# Review_PCD_1_2.net
KiCad netlist of a schematic drawn in EAGLE
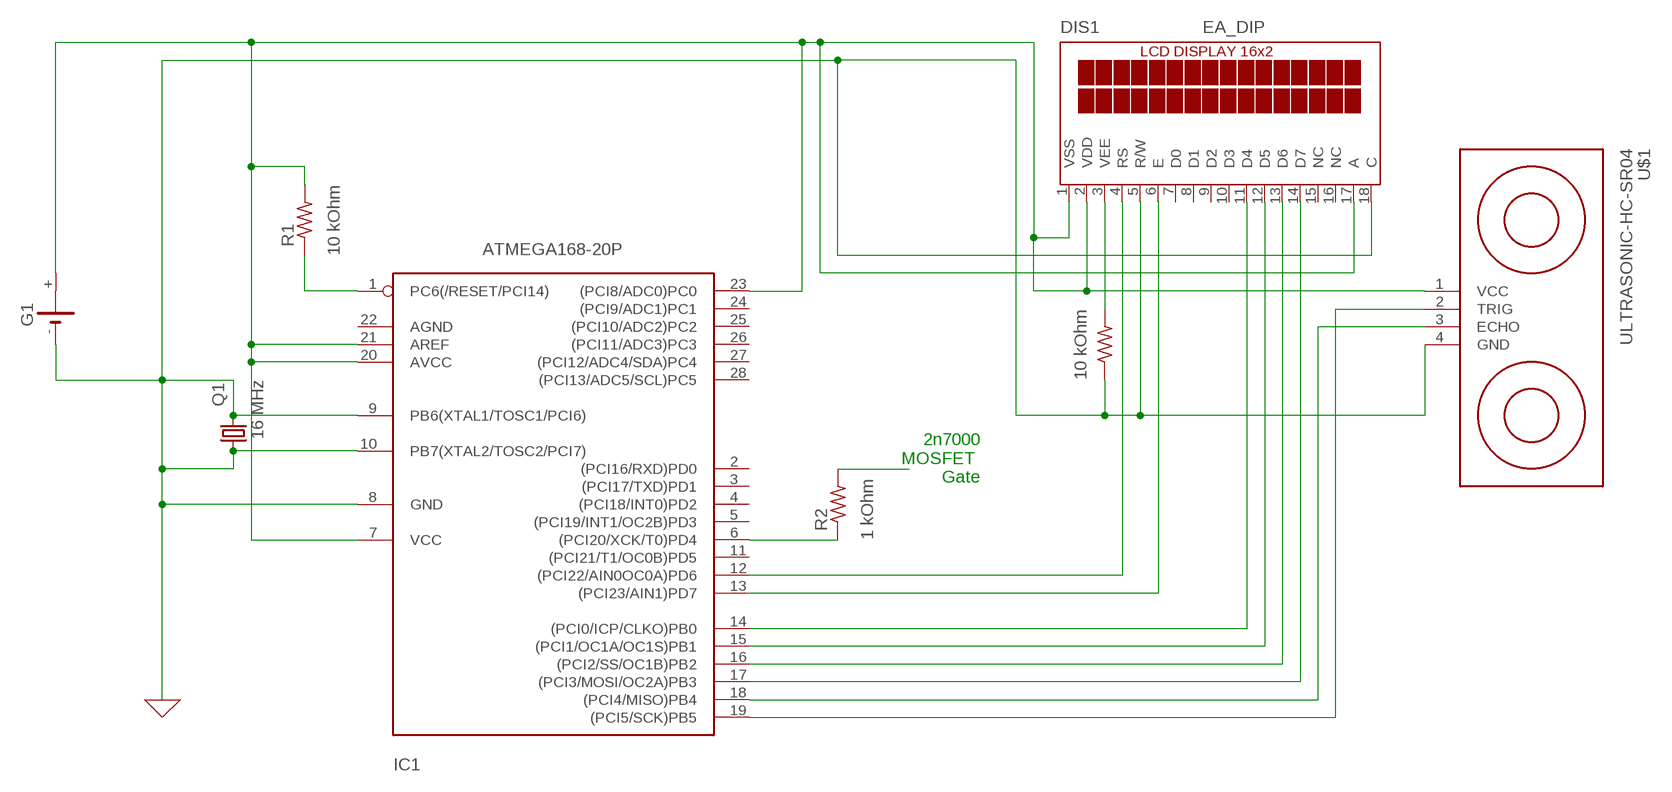
[diagram p0: schematic, sheet 1]

(export (version "E")
  (design (tool "Eeschema 10.0.6"))
  (components
    (comp (ref "DIS1")
      (value "EA_DIP")
      (footprint "eagle-import:EA_DIP")
      (libsource (lib "eagle-import") (part "EA_DIP"))
    )
    (comp (ref "G1")
      (value "CR1/2")
      (footprint "eagle-import:CR1_2")
      (libsource (lib "eagle-import") (part "CR1/2"))
    )
    (comp (ref "IC1")
      (value "ATMEGA168-20P")
      (footprint "eagle-import:DIL28-3")
      (libsource (lib "eagle-import") (part "ATMEGA168P-20"))
    )
    (comp (ref "Q1")
      (value "KX-4")
      (footprint "eagle-import:1.6X1.2")
      (fields (field (name "Q1") "16 MHz"))
      (libsource (lib "eagle-import") (part "KX-4"))
    )
    (comp (ref "R1")
      (value "R-US_R2012W")
      (footprint "eagle-import:R2012W")
      (fields (field (name "R1") "10 kOhm"))
      (libsource (lib "eagle-import") (part "R-US_R2012W"))
    )
    (comp (ref "R2")
      (value "R-US_R2012W")
      (footprint "eagle-import:R2012W")
      (fields (field (name "R1") "1 kOhm"))
      (libsource (lib "eagle-import") (part "R-US_R2012W"))
    )
    (comp (ref "R3")
      (value "R-US_R2012W")
      (footprint "eagle-import:R2012W")
      (fields (field (name "R1") "10 kOhm"))
      (libsource (lib "eagle-import") (part "R-US_R2012W"))
    )
    (comp (ref "U$1")
      (value "ULTRASONIC-HC-SR04")
      (footprint "eagle-import:ULTRASONIC-HC-SR04")
      (libsource (lib "eagle-import") (part "ULTRASONIC-HC-SR04"))
    )
  )
  (nets
    (net (code "1") (name "GND") (class "Default")
      (node (ref "DIS1") (pin "18") (pinfunction "C_18") (pintype "passive"))
      (node (ref "DIS1") (pin "5") (pinfunction "R/W_5") (pintype "input"))
      (node (ref "G1") (pin "-") (pinfunction "-_-") (pintype "passive"))
      (node (ref "IC1") (pin "10") (pinfunction "PB7(XTAL2/TOSC2/PCI7)_10") (pintype "bidirectional"))
      (node (ref "IC1") (pin "8") (pinfunction "GND_8") (pintype "bidirectional"))
      (node (ref "IC1") (pin "9") (pinfunction "PB6(XTAL1/TOSC1/PCI6)_9") (pintype "bidirectional"))
      (node (ref "Q1") (pin "1") (pinfunction "1_1") (pintype "passive"))
      (node (ref "Q1") (pin "3") (pinfunction "2_3") (pintype "passive"))
      (node (ref "R3") (pin "1") (pinfunction "1_1") (pintype "passive"))
      (node (ref "U$1") (pin "4") (pinfunction "GND_4") (pintype "power_in"))
    )
    (net (code "2") (name "Net-(DIS1-A)") (class "Default")
      (node (ref "DIS1") (pin "1") (pinfunction "VSS_1") (pintype "power_in"))
      (node (ref "DIS1") (pin "17") (pinfunction "A_17") (pintype "passive"))
      (node (ref "DIS1") (pin "2") (pinfunction "VDD_2") (pintype "power_in"))
      (node (ref "G1") (pin "+") (pinfunction "+_+") (pintype "passive"))
      (node (ref "IC1") (pin "20") (pinfunction "AVCC_20") (pintype "bidirectional"))
      (node (ref "IC1") (pin "21") (pinfunction "AREF_21") (pintype "bidirectional"))
      (node (ref "IC1") (pin "23") (pinfunction "(PCI8/ADC0)PC0_23") (pintype "bidirectional"))
      (node (ref "IC1") (pin "7") (pinfunction "VCC_7") (pintype "bidirectional"))
      (node (ref "R1") (pin "2") (pinfunction "2_2") (pintype "passive"))
      (node (ref "U$1") (pin "1") (pinfunction "VCC_1") (pintype "power_in"))
    )
    (net (code "3") (name "Net-(DIS1-D4)") (class "Default")
      (node (ref "DIS1") (pin "11") (pinfunction "D4_11") (pintype "input"))
      (node (ref "IC1") (pin "14") (pinfunction "(PCI0/ICP/CLKO)PB0_14") (pintype "bidirectional"))
    )
    (net (code "4") (name "Net-(DIS1-D5)") (class "Default")
      (node (ref "DIS1") (pin "12") (pinfunction "D5_12") (pintype "input"))
      (node (ref "IC1") (pin "15") (pinfunction "(PCI1/OC1A/OC1S)PB1_15") (pintype "bidirectional"))
    )
    (net (code "5") (name "Net-(DIS1-D6)") (class "Default")
      (node (ref "DIS1") (pin "13") (pinfunction "D6_13") (pintype "input"))
      (node (ref "IC1") (pin "16") (pinfunction "(PCI2/SS/OC1B)PB2_16") (pintype "bidirectional"))
    )
    (net (code "6") (name "Net-(DIS1-D7)") (class "Default")
      (node (ref "DIS1") (pin "14") (pinfunction "D7_14") (pintype "input"))
      (node (ref "IC1") (pin "17") (pinfunction "(PCI3/MOSI/OC2A)PB3_17") (pintype "bidirectional"))
    )
    (net (code "7") (name "Net-(DIS1-E)") (class "Default")
      (node (ref "DIS1") (pin "6") (pinfunction "E_6") (pintype "input"))
      (node (ref "IC1") (pin "13") (pinfunction "(PCI23/AIN1)PD7_13") (pintype "bidirectional"))
    )
    (net (code "8") (name "Net-(DIS1-RS)") (class "Default")
      (node (ref "DIS1") (pin "4") (pinfunction "RS_4") (pintype "input"))
      (node (ref "IC1") (pin "12") (pinfunction "(PCI22/AIN0OC0A)PD6_12") (pintype "bidirectional"))
    )
    (net (code "9") (name "Net-(DIS1-VEE)") (class "Default")
      (node (ref "DIS1") (pin "3") (pinfunction "VEE_3") (pintype "power_in"))
      (node (ref "R3") (pin "2") (pinfunction "2_2") (pintype "passive"))
    )
    (net (code "10") (name "Net-(IC1-(PCI4{slash}MISO)PB4)") (class "Default")
      (node (ref "IC1") (pin "18") (pinfunction "(PCI4/MISO)PB4_18") (pintype "bidirectional"))
      (node (ref "U$1") (pin "3") (pinfunction "ECHO_3") (pintype "output"))
    )
    (net (code "11") (name "Net-(IC1-(PCI5{slash}SCK)PB5)") (class "Default")
      (node (ref "IC1") (pin "19") (pinfunction "(PCI5/SCK)PB5_19") (pintype "bidirectional"))
      (node (ref "U$1") (pin "2") (pinfunction "TRIG_2") (pintype "input"))
    )
    (net (code "12") (name "Net-(IC1-(PCI20{slash}XCK{slash}T0)PD4)") (class "Default")
      (node (ref "IC1") (pin "6") (pinfunction "(PCI20/XCK/T0)PD4_6") (pintype "bidirectional"))
      (node (ref "R2") (pin "1") (pinfunction "1_1") (pintype "passive"))
    )
    (net (code "13") (name "Net-(IC1-PC6({slash}RESET{slash}PCI14))") (class "Default")
      (node (ref "IC1") (pin "1") (pinfunction "PC6(/RESET/PCI14)_1") (pintype "bidirectional"))
      (node (ref "R1") (pin "1") (pinfunction "1_1") (pintype "passive"))
    )
    (net (code "14") (name "unconnected-(DIS1-D0-Pad7)") (class "Default")
      (node (ref "DIS1") (pin "7") (pinfunction "D0_7") (pintype "input"))
    )
    (net (code "15") (name "unconnected-(DIS1-D1-Pad8)") (class "Default")
      (node (ref "DIS1") (pin "8") (pinfunction "D1_8") (pintype "input"))
    )
    (net (code "16") (name "unconnected-(DIS1-D2-Pad9)") (class "Default")
      (node (ref "DIS1") (pin "9") (pinfunction "D2_9") (pintype "input"))
    )
    (net (code "17") (name "unconnected-(DIS1-D3-Pad10)") (class "Default")
      (node (ref "DIS1") (pin "10") (pinfunction "D3_10") (pintype "input"))
    )
    (net (code "18") (name "unconnected-(DIS1-NC-Pad15)") (class "Default")
      (node (ref "DIS1") (pin "15") (pinfunction "NC_15") (pintype "no_connect"))
    )
    (net (code "19") (name "unconnected-(DIS1-NC-Pad16)") (class "Default")
      (node (ref "DIS1") (pin "16") (pinfunction "NC_16") (pintype "no_connect"))
    )
    (net (code "20") (name "unconnected-(G1-+-Pad+@1)") (class "Default")
      (node (ref "G1") (pin "+@1") (pinfunction "+_+@1") (pintype "passive"))
    )
    (net (code "21") (name "unconnected-(IC1-(PCI9{slash}ADC1)PC1-Pad24)") (class "Default")
      (node (ref "IC1") (pin "24") (pinfunction "(PCI9/ADC1)PC1_24") (pintype "bidirectional"))
    )
    (net (code "22") (name "unconnected-(IC1-(PCI10{slash}ADC2)PC2-Pad25)") (class "Default")
      (node (ref "IC1") (pin "25") (pinfunction "(PCI10/ADC2)PC2_25") (pintype "bidirectional"))
    )
    (net (code "23") (name "unconnected-(IC1-(PCI11{slash}ADC3)PC3-Pad26)") (class "Default")
      (node (ref "IC1") (pin "26") (pinfunction "(PCI11/ADC3)PC3_26") (pintype "bidirectional"))
    )
    (net (code "24") (name "unconnected-(IC1-(PCI12{slash}ADC4{slash}SDA)PC4-Pad27)") (class "Default")
      (node (ref "IC1") (pin "27") (pinfunction "(PCI12/ADC4/SDA)PC4_27") (pintype "bidirectional"))
    )
    (net (code "25") (name "unconnected-(IC1-(PCI13{slash}ADC5{slash}SCL)PC5-Pad28)") (class "Default")
      (node (ref "IC1") (pin "28") (pinfunction "(PCI13/ADC5/SCL)PC5_28") (pintype "bidirectional"))
    )
    (net (code "26") (name "unconnected-(IC1-(PCI16{slash}RXD)PD0-Pad2)") (class "Default")
      (node (ref "IC1") (pin "2") (pinfunction "(PCI16/RXD)PD0_2") (pintype "bidirectional"))
    )
    (net (code "27") (name "unconnected-(IC1-(PCI17{slash}TXD)PD1-Pad3)") (class "Default")
      (node (ref "IC1") (pin "3") (pinfunction "(PCI17/TXD)PD1_3") (pintype "bidirectional"))
    )
    (net (code "28") (name "unconnected-(IC1-(PCI18{slash}INT0)PD2-Pad4)") (class "Default")
      (node (ref "IC1") (pin "4") (pinfunction "(PCI18/INT0)PD2_4") (pintype "bidirectional"))
    )
    (net (code "29") (name "unconnected-(IC1-(PCI19{slash}INT1{slash}OC2B)PD3-Pad5)") (class "Default")
      (node (ref "IC1") (pin "5") (pinfunction "(PCI19/INT1/OC2B)PD3_5") (pintype "bidirectional"))
    )
    (net (code "30") (name "unconnected-(IC1-(PCI21{slash}T1{slash}OC0B)PD5-Pad11)") (class "Default")
      (node (ref "IC1") (pin "11") (pinfunction "(PCI21/T1/OC0B)PD5_11") (pintype "bidirectional"))
    )
    (net (code "31") (name "unconnected-(IC1-AGND-Pad22)") (class "Default")
      (node (ref "IC1") (pin "22") (pinfunction "AGND_22") (pintype "bidirectional"))
    )
    (net (code "32") (name "unconnected-(R2-Pad2)") (class "Default")
      (node (ref "R2") (pin "2") (pinfunction "2_2") (pintype "passive"))
    )
  )
)
